# schematics.net
KiCad netlist of a schematic drawn in EasyEDA
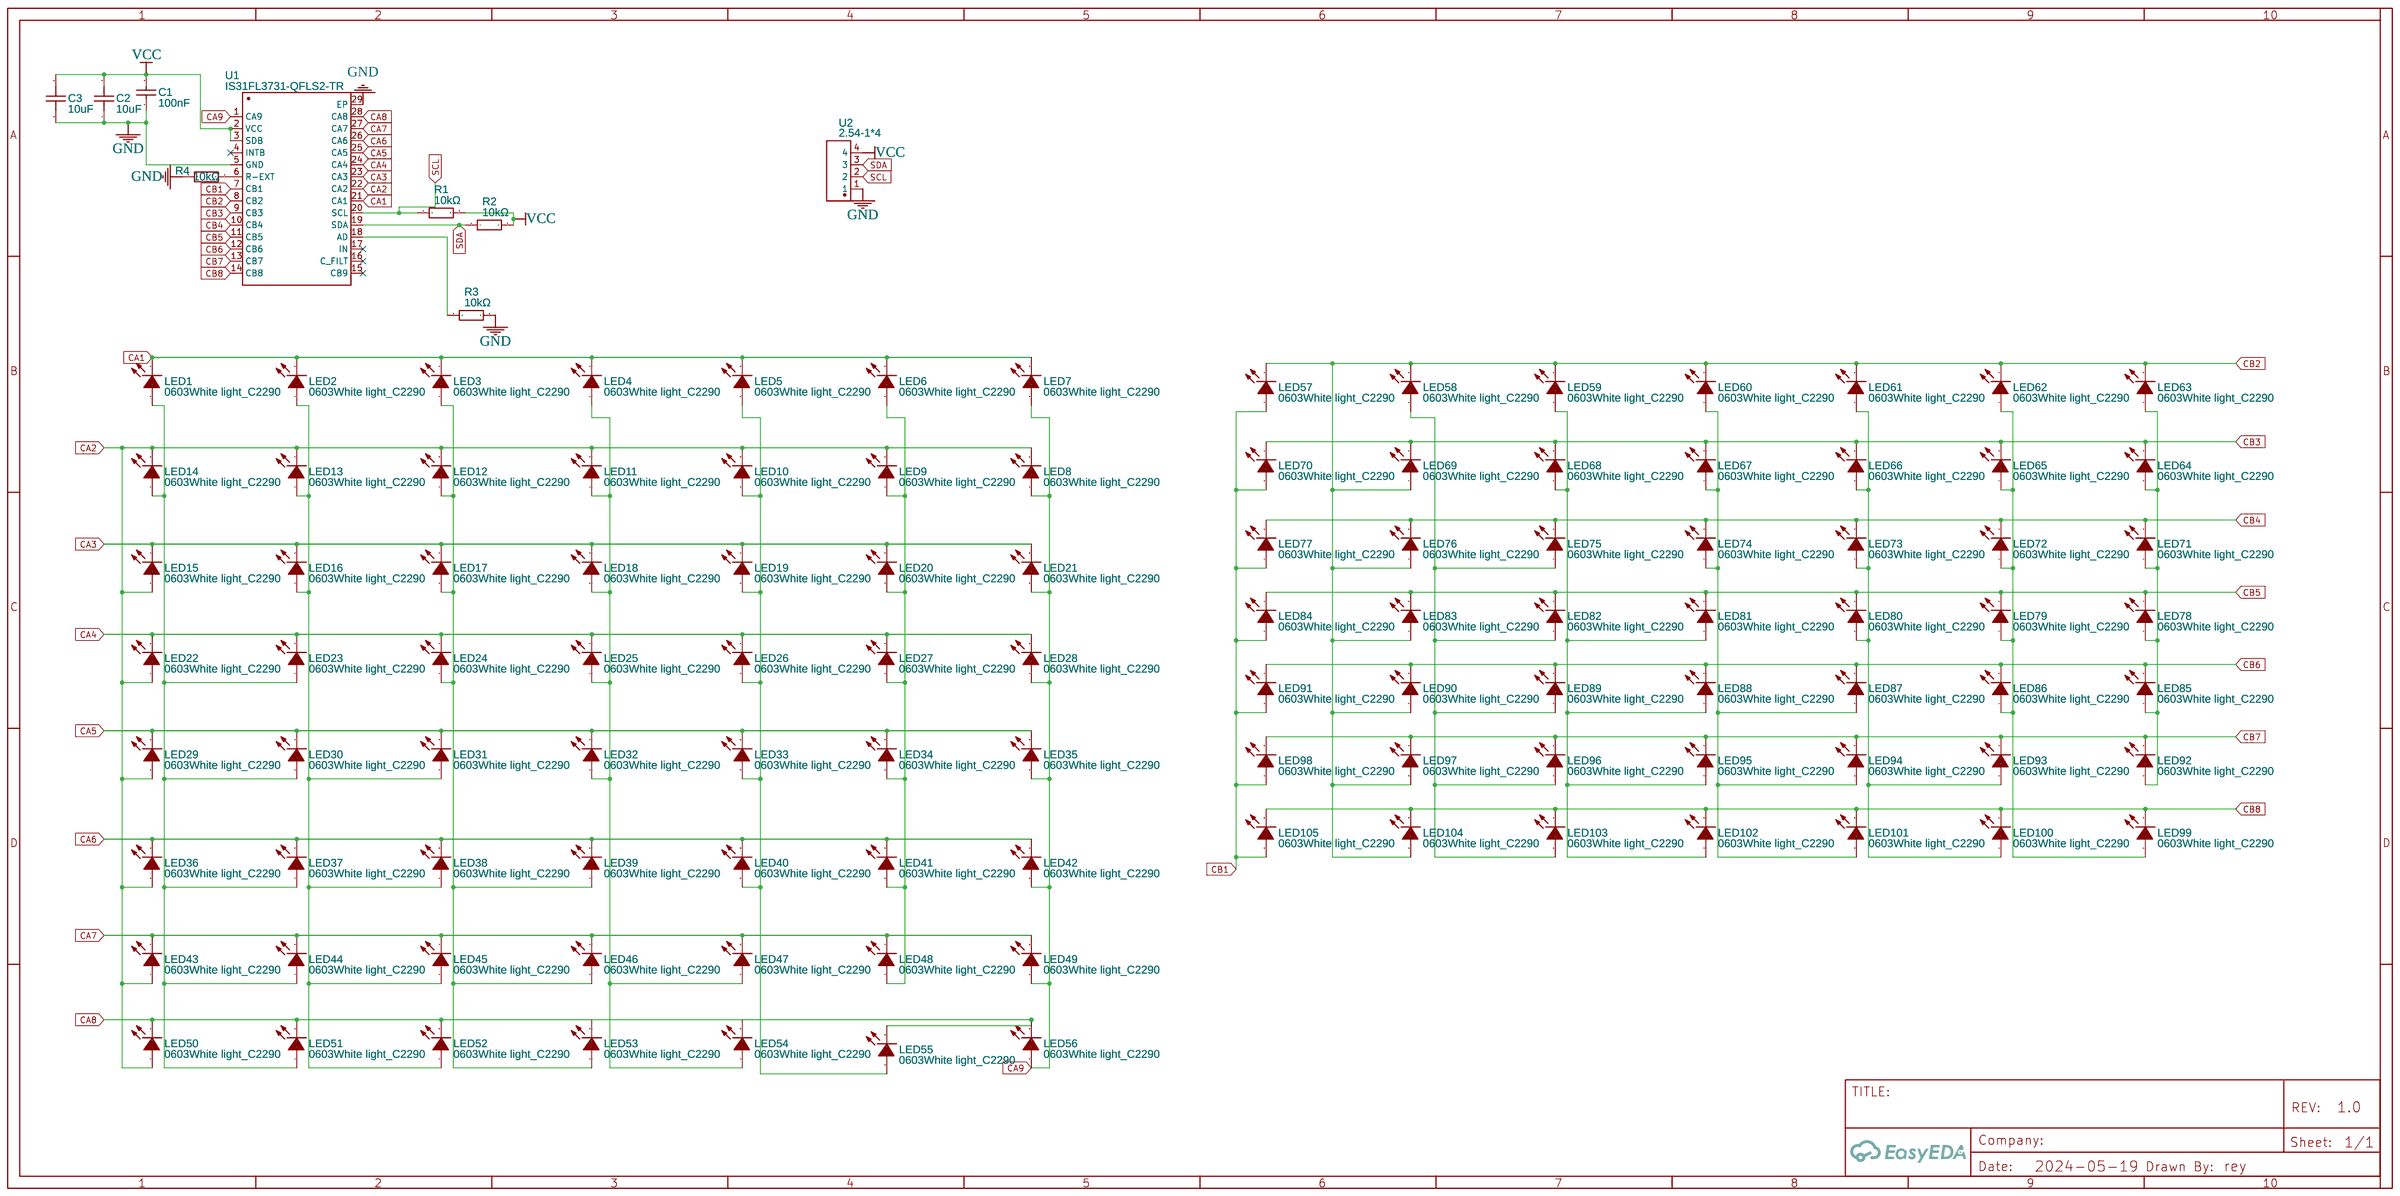
[diagram p0: schematic sheet]

(export (version "E")
  (design (tool "Eeschema 10.0.6"))
  (components
    (comp (ref "C1")
      (value "100nF")
      (fields
        (field (name "Manufacturer Part") "CL05B104KO5NNNC")
        (field (name "Manufacturer") "SAMSUNG(三星)")
      )
      (libsource (lib "") (part "CL05B104KO5NNNC"))
    )
    (comp (ref "C2")
      (value "10uF")
      (fields
        (field (name "Manufacturer Part") "CL10A106KP8NNNC")
        (field (name "Manufacturer") "SAMSUNG(三星)")
      )
      (libsource (lib "") (part "CL10A106KP8NNNC"))
    )
    (comp (ref "C3")
      (value "10uF")
      (fields
        (field (name "Manufacturer Part") "CL10A106KP8NNNC")
        (field (name "Manufacturer") "SAMSUNG(三星)")
      )
      (libsource (lib "") (part "CL10A106KP8NNNC"))
    )
    (comp (ref "LED1")
      (value "0603White light_C2290")
      (fields (field (name "Manufacturer Part") "KT-0603白灯") (field (name "Manufacturer") "KENTO"))
      (libsource (lib "") (part "0603White light_C2290"))
    )
    (comp (ref "LED2")
      (value "0603White light_C2290")
      (fields (field (name "Manufacturer Part") "KT-0603白灯") (field (name "Manufacturer") "KENTO"))
      (libsource (lib "") (part "0603White light_C2290"))
    )
    (comp (ref "LED3")
      (value "0603White light_C2290")
      (fields (field (name "Manufacturer Part") "KT-0603白灯") (field (name "Manufacturer") "KENTO"))
      (libsource (lib "") (part "0603White light_C2290"))
    )
    (comp (ref "LED4")
      (value "0603White light_C2290")
      (fields (field (name "Manufacturer Part") "KT-0603白灯") (field (name "Manufacturer") "KENTO"))
      (libsource (lib "") (part "0603White light_C2290"))
    )
    (comp (ref "LED5")
      (value "0603White light_C2290")
      (fields (field (name "Manufacturer Part") "KT-0603白灯") (field (name "Manufacturer") "KENTO"))
      (libsource (lib "") (part "0603White light_C2290"))
    )
    (comp (ref "LED6")
      (value "0603White light_C2290")
      (fields (field (name "Manufacturer Part") "KT-0603白灯") (field (name "Manufacturer") "KENTO"))
      (libsource (lib "") (part "0603White light_C2290"))
    )
    (comp (ref "LED7")
      (value "0603White light_C2290")
      (fields (field (name "Manufacturer Part") "KT-0603白灯") (field (name "Manufacturer") "KENTO"))
      (libsource (lib "") (part "0603White light_C2290"))
    )
    (comp (ref "LED8")
      (value "0603White light_C2290")
      (fields (field (name "Manufacturer Part") "KT-0603白灯") (field (name "Manufacturer") "KENTO"))
      (libsource (lib "") (part "0603White light_C2290"))
    )
    (comp (ref "LED9")
      (value "0603White light_C2290")
      (fields (field (name "Manufacturer Part") "KT-0603白灯") (field (name "Manufacturer") "KENTO"))
      (libsource (lib "") (part "0603White light_C2290"))
    )
    (comp (ref "LED10")
      (value "0603White light_C2290")
      (fields (field (name "Manufacturer Part") "KT-0603白灯") (field (name "Manufacturer") "KENTO"))
      (libsource (lib "") (part "0603White light_C2290"))
    )
    (comp (ref "LED11")
      (value "0603White light_C2290")
      (fields (field (name "Manufacturer Part") "KT-0603白灯") (field (name "Manufacturer") "KENTO"))
      (libsource (lib "") (part "0603White light_C2290"))
    )
    (comp (ref "LED12")
      (value "0603White light_C2290")
      (fields (field (name "Manufacturer Part") "KT-0603白灯") (field (name "Manufacturer") "KENTO"))
      (libsource (lib "") (part "0603White light_C2290"))
    )
    (comp (ref "LED13")
      (value "0603White light_C2290")
      (fields (field (name "Manufacturer Part") "KT-0603白灯") (field (name "Manufacturer") "KENTO"))
      (libsource (lib "") (part "0603White light_C2290"))
    )
    (comp (ref "LED14")
      (value "0603White light_C2290")
      (fields (field (name "Manufacturer Part") "KT-0603白灯") (field (name "Manufacturer") "KENTO"))
      (libsource (lib "") (part "0603White light_C2290"))
    )
    (comp (ref "LED15")
      (value "0603White light_C2290")
      (fields (field (name "Manufacturer Part") "KT-0603白灯") (field (name "Manufacturer") "KENTO"))
      (libsource (lib "") (part "0603White light_C2290"))
    )
    (comp (ref "LED16")
      (value "0603White light_C2290")
      (fields (field (name "Manufacturer Part") "KT-0603白灯") (field (name "Manufacturer") "KENTO"))
      (libsource (lib "") (part "0603White light_C2290"))
    )
    (comp (ref "LED17")
      (value "0603White light_C2290")
      (fields (field (name "Manufacturer Part") "KT-0603白灯") (field (name "Manufacturer") "KENTO"))
      (libsource (lib "") (part "0603White light_C2290"))
    )
    (comp (ref "LED18")
      (value "0603White light_C2290")
      (fields (field (name "Manufacturer Part") "KT-0603白灯") (field (name "Manufacturer") "KENTO"))
      (libsource (lib "") (part "0603White light_C2290"))
    )
    (comp (ref "LED19")
      (value "0603White light_C2290")
      (fields (field (name "Manufacturer Part") "KT-0603白灯") (field (name "Manufacturer") "KENTO"))
      (libsource (lib "") (part "0603White light_C2290"))
    )
    (comp (ref "LED20")
      (value "0603White light_C2290")
      (fields (field (name "Manufacturer Part") "KT-0603白灯") (field (name "Manufacturer") "KENTO"))
      (libsource (lib "") (part "0603White light_C2290"))
    )
    (comp (ref "LED21")
      (value "0603White light_C2290")
      (fields (field (name "Manufacturer Part") "KT-0603白灯") (field (name "Manufacturer") "KENTO"))
      (libsource (lib "") (part "0603White light_C2290"))
    )
    (comp (ref "LED22")
      (value "0603White light_C2290")
      (fields (field (name "Manufacturer Part") "KT-0603白灯") (field (name "Manufacturer") "KENTO"))
      (libsource (lib "") (part "0603White light_C2290"))
    )
    (comp (ref "LED23")
      (value "0603White light_C2290")
      (fields (field (name "Manufacturer Part") "KT-0603白灯") (field (name "Manufacturer") "KENTO"))
      (libsource (lib "") (part "0603White light_C2290"))
    )
    (comp (ref "LED24")
      (value "0603White light_C2290")
      (fields (field (name "Manufacturer Part") "KT-0603白灯") (field (name "Manufacturer") "KENTO"))
      (libsource (lib "") (part "0603White light_C2290"))
    )
    (comp (ref "LED25")
      (value "0603White light_C2290")
      (fields (field (name "Manufacturer Part") "KT-0603白灯") (field (name "Manufacturer") "KENTO"))
      (libsource (lib "") (part "0603White light_C2290"))
    )
    (comp (ref "LED26")
      (value "0603White light_C2290")
      (fields (field (name "Manufacturer Part") "KT-0603白灯") (field (name "Manufacturer") "KENTO"))
      (libsource (lib "") (part "0603White light_C2290"))
    )
    (comp (ref "LED27")
      (value "0603White light_C2290")
      (fields (field (name "Manufacturer Part") "KT-0603白灯") (field (name "Manufacturer") "KENTO"))
      (libsource (lib "") (part "0603White light_C2290"))
    )
    (comp (ref "LED28")
      (value "0603White light_C2290")
      (fields (field (name "Manufacturer Part") "KT-0603白灯") (field (name "Manufacturer") "KENTO"))
      (libsource (lib "") (part "0603White light_C2290"))
    )
    (comp (ref "LED29")
      (value "0603White light_C2290")
      (fields (field (name "Manufacturer Part") "KT-0603白灯") (field (name "Manufacturer") "KENTO"))
      (libsource (lib "") (part "0603White light_C2290"))
    )
    (comp (ref "LED30")
      (value "0603White light_C2290")
      (fields (field (name "Manufacturer Part") "KT-0603白灯") (field (name "Manufacturer") "KENTO"))
      (libsource (lib "") (part "0603White light_C2290"))
    )
    (comp (ref "LED31")
      (value "0603White light_C2290")
      (fields (field (name "Manufacturer Part") "KT-0603白灯") (field (name "Manufacturer") "KENTO"))
      (libsource (lib "") (part "0603White light_C2290"))
    )
    (comp (ref "LED32")
      (value "0603White light_C2290")
      (fields (field (name "Manufacturer Part") "KT-0603白灯") (field (name "Manufacturer") "KENTO"))
      (libsource (lib "") (part "0603White light_C2290"))
    )
    (comp (ref "LED33")
      (value "0603White light_C2290")
      (fields (field (name "Manufacturer Part") "KT-0603白灯") (field (name "Manufacturer") "KENTO"))
      (libsource (lib "") (part "0603White light_C2290"))
    )
    (comp (ref "LED34")
      (value "0603White light_C2290")
      (fields (field (name "Manufacturer Part") "KT-0603白灯") (field (name "Manufacturer") "KENTO"))
      (libsource (lib "") (part "0603White light_C2290"))
    )
    (comp (ref "LED35")
      (value "0603White light_C2290")
      (fields (field (name "Manufacturer Part") "KT-0603白灯") (field (name "Manufacturer") "KENTO"))
      (libsource (lib "") (part "0603White light_C2290"))
    )
    (comp (ref "LED36")
      (value "0603White light_C2290")
      (fields (field (name "Manufacturer Part") "KT-0603白灯") (field (name "Manufacturer") "KENTO"))
      (libsource (lib "") (part "0603White light_C2290"))
    )
    (comp (ref "LED37")
      (value "0603White light_C2290")
      (fields (field (name "Manufacturer Part") "KT-0603白灯") (field (name "Manufacturer") "KENTO"))
      (libsource (lib "") (part "0603White light_C2290"))
    )
    (comp (ref "LED38")
      (value "0603White light_C2290")
      (fields (field (name "Manufacturer Part") "KT-0603白灯") (field (name "Manufacturer") "KENTO"))
      (libsource (lib "") (part "0603White light_C2290"))
    )
    (comp (ref "LED39")
      (value "0603White light_C2290")
      (fields (field (name "Manufacturer Part") "KT-0603白灯") (field (name "Manufacturer") "KENTO"))
      (libsource (lib "") (part "0603White light_C2290"))
    )
    (comp (ref "LED40")
      (value "0603White light_C2290")
      (fields (field (name "Manufacturer Part") "KT-0603白灯") (field (name "Manufacturer") "KENTO"))
      (libsource (lib "") (part "0603White light_C2290"))
    )
    (comp (ref "LED41")
      (value "0603White light_C2290")
      (fields (field (name "Manufacturer Part") "KT-0603白灯") (field (name "Manufacturer") "KENTO"))
      (libsource (lib "") (part "0603White light_C2290"))
    )
    (comp (ref "LED42")
      (value "0603White light_C2290")
      (fields (field (name "Manufacturer Part") "KT-0603白灯") (field (name "Manufacturer") "KENTO"))
      (libsource (lib "") (part "0603White light_C2290"))
    )
    (comp (ref "LED43")
      (value "0603White light_C2290")
      (fields (field (name "Manufacturer Part") "KT-0603白灯") (field (name "Manufacturer") "KENTO"))
      (libsource (lib "") (part "0603White light_C2290"))
    )
    (comp (ref "LED44")
      (value "0603White light_C2290")
      (fields (field (name "Manufacturer Part") "KT-0603白灯") (field (name "Manufacturer") "KENTO"))
      (libsource (lib "") (part "0603White light_C2290"))
    )
    (comp (ref "LED45")
      (value "0603White light_C2290")
      (fields (field (name "Manufacturer Part") "KT-0603白灯") (field (name "Manufacturer") "KENTO"))
      (libsource (lib "") (part "0603White light_C2290"))
    )
    (comp (ref "LED46")
      (value "0603White light_C2290")
      (fields (field (name "Manufacturer Part") "KT-0603白灯") (field (name "Manufacturer") "KENTO"))
      (libsource (lib "") (part "0603White light_C2290"))
    )
    (comp (ref "LED47")
      (value "0603White light_C2290")
      (fields (field (name "Manufacturer Part") "KT-0603白灯") (field (name "Manufacturer") "KENTO"))
      (libsource (lib "") (part "0603White light_C2290"))
    )
    (comp (ref "LED48")
      (value "0603White light_C2290")
      (fields (field (name "Manufacturer Part") "KT-0603白灯") (field (name "Manufacturer") "KENTO"))
      (libsource (lib "") (part "0603White light_C2290"))
    )
    (comp (ref "LED49")
      (value "0603White light_C2290")
      (fields (field (name "Manufacturer Part") "KT-0603白灯") (field (name "Manufacturer") "KENTO"))
      (libsource (lib "") (part "0603White light_C2290"))
    )
    (comp (ref "LED50")
      (value "0603White light_C2290")
      (fields (field (name "Manufacturer Part") "KT-0603白灯") (field (name "Manufacturer") "KENTO"))
      (libsource (lib "") (part "0603White light_C2290"))
    )
    (comp (ref "LED51")
      (value "0603White light_C2290")
      (fields (field (name "Manufacturer Part") "KT-0603白灯") (field (name "Manufacturer") "KENTO"))
      (libsource (lib "") (part "0603White light_C2290"))
    )
    (comp (ref "LED52")
      (value "0603White light_C2290")
      (fields (field (name "Manufacturer Part") "KT-0603白灯") (field (name "Manufacturer") "KENTO"))
      (libsource (lib "") (part "0603White light_C2290"))
    )
    (comp (ref "LED53")
      (value "0603White light_C2290")
      (fields (field (name "Manufacturer Part") "KT-0603白灯") (field (name "Manufacturer") "KENTO"))
      (libsource (lib "") (part "0603White light_C2290"))
    )
    (comp (ref "LED54")
      (value "0603White light_C2290")
      (fields (field (name "Manufacturer Part") "KT-0603白灯") (field (name "Manufacturer") "KENTO"))
      (libsource (lib "") (part "0603White light_C2290"))
    )
    (comp (ref "LED55")
      (value "0603White light_C2290")
      (fields (field (name "Manufacturer Part") "KT-0603白灯") (field (name "Manufacturer") "KENTO"))
      (libsource (lib "") (part "0603White light_C2290"))
    )
    (comp (ref "LED56")
      (value "0603White light_C2290")
      (fields (field (name "Manufacturer Part") "KT-0603白灯") (field (name "Manufacturer") "KENTO"))
      (libsource (lib "") (part "0603White light_C2290"))
    )
    (comp (ref "LED57")
      (value "0603White light_C2290")
      (fields (field (name "Manufacturer Part") "KT-0603白灯") (field (name "Manufacturer") "KENTO"))
      (libsource (lib "") (part "0603White light_C2290_1"))
    )
    (comp (ref "LED58")
      (value "0603White light_C2290")
      (fields (field (name "Manufacturer Part") "KT-0603白灯") (field (name "Manufacturer") "KENTO"))
      (libsource (lib "") (part "0603White light_C2290_1"))
    )
    (comp (ref "LED59")
      (value "0603White light_C2290")
      (fields (field (name "Manufacturer Part") "KT-0603白灯") (field (name "Manufacturer") "KENTO"))
      (libsource (lib "") (part "0603White light_C2290_1"))
    )
    (comp (ref "LED60")
      (value "0603White light_C2290")
      (fields (field (name "Manufacturer Part") "KT-0603白灯") (field (name "Manufacturer") "KENTO"))
      (libsource (lib "") (part "0603White light_C2290_1"))
    )
    (comp (ref "LED61")
      (value "0603White light_C2290")
      (fields (field (name "Manufacturer Part") "KT-0603白灯") (field (name "Manufacturer") "KENTO"))
      (libsource (lib "") (part "0603White light_C2290_1"))
    )
    (comp (ref "LED62")
      (value "0603White light_C2290")
      (fields (field (name "Manufacturer Part") "KT-0603白灯") (field (name "Manufacturer") "KENTO"))
      (libsource (lib "") (part "0603White light_C2290_1"))
    )
    (comp (ref "LED63")
      (value "0603White light_C2290")
      (fields (field (name "Manufacturer Part") "KT-0603白灯") (field (name "Manufacturer") "KENTO"))
      (libsource (lib "") (part "0603White light_C2290_1"))
    )
    (comp (ref "LED64")
      (value "0603White light_C2290")
      (fields (field (name "Manufacturer Part") "KT-0603白灯") (field (name "Manufacturer") "KENTO"))
      (libsource (lib "") (part "0603White light_C2290_1"))
    )
    (comp (ref "LED65")
      (value "0603White light_C2290")
      (fields (field (name "Manufacturer Part") "KT-0603白灯") (field (name "Manufacturer") "KENTO"))
      (libsource (lib "") (part "0603White light_C2290_1"))
    )
    (comp (ref "LED66")
      (value "0603White light_C2290")
      (fields (field (name "Manufacturer Part") "KT-0603白灯") (field (name "Manufacturer") "KENTO"))
      (libsource (lib "") (part "0603White light_C2290_1"))
    )
    (comp (ref "LED67")
      (value "0603White light_C2290")
      (fields (field (name "Manufacturer Part") "KT-0603白灯") (field (name "Manufacturer") "KENTO"))
      (libsource (lib "") (part "0603White light_C2290_1"))
    )
    (comp (ref "LED68")
      (value "0603White light_C2290")
      (fields (field (name "Manufacturer Part") "KT-0603白灯") (field (name "Manufacturer") "KENTO"))
      (libsource (lib "") (part "0603White light_C2290_1"))
    )
    (comp (ref "LED69")
      (value "0603White light_C2290")
      (fields (field (name "Manufacturer Part") "KT-0603白灯") (field (name "Manufacturer") "KENTO"))
      (libsource (lib "") (part "0603White light_C2290_1"))
    )
    (comp (ref "LED70")
      (value "0603White light_C2290")
      (fields (field (name "Manufacturer Part") "KT-0603白灯") (field (name "Manufacturer") "KENTO"))
      (libsource (lib "") (part "0603White light_C2290_1"))
    )
    (comp (ref "LED71")
      (value "0603White light_C2290")
      (fields (field (name "Manufacturer Part") "KT-0603白灯") (field (name "Manufacturer") "KENTO"))
      (libsource (lib "") (part "0603White light_C2290_1"))
    )
    (comp (ref "LED72")
      (value "0603White light_C2290")
      (fields (field (name "Manufacturer Part") "KT-0603白灯") (field (name "Manufacturer") "KENTO"))
      (libsource (lib "") (part "0603White light_C2290_1"))
    )
    (comp (ref "LED73")
      (value "0603White light_C2290")
      (fields (field (name "Manufacturer Part") "KT-0603白灯") (field (name "Manufacturer") "KENTO"))
      (libsource (lib "") (part "0603White light_C2290_1"))
    )
    (comp (ref "LED74")
      (value "0603White light_C2290")
      (fields (field (name "Manufacturer Part") "KT-0603白灯") (field (name "Manufacturer") "KENTO"))
      (libsource (lib "") (part "0603White light_C2290_1"))
    )
    (comp (ref "LED75")
      (value "0603White light_C2290")
      (fields (field (name "Manufacturer Part") "KT-0603白灯") (field (name "Manufacturer") "KENTO"))
      (libsource (lib "") (part "0603White light_C2290_1"))
    )
    (comp (ref "LED76")
      (value "0603White light_C2290")
      (fields (field (name "Manufacturer Part") "KT-0603白灯") (field (name "Manufacturer") "KENTO"))
      (libsource (lib "") (part "0603White light_C2290_1"))
    )
    (comp (ref "LED77")
      (value "0603White light_C2290")
      (fields (field (name "Manufacturer Part") "KT-0603白灯") (field (name "Manufacturer") "KENTO"))
      (libsource (lib "") (part "0603White light_C2290_1"))
    )
    (comp (ref "LED78")
      (value "0603White light_C2290")
      (fields (field (name "Manufacturer Part") "KT-0603白灯") (field (name "Manufacturer") "KENTO"))
      (libsource (lib "") (part "0603White light_C2290_1"))
    )
    (comp (ref "LED79")
      (value "0603White light_C2290")
      (fields (field (name "Manufacturer Part") "KT-0603白灯") (field (name "Manufacturer") "KENTO"))
      (libsource (lib "") (part "0603White light_C2290_1"))
    )
    (comp (ref "LED80")
      (value "0603White light_C2290")
      (fields (field (name "Manufacturer Part") "KT-0603白灯") (field (name "Manufacturer") "KENTO"))
      (libsource (lib "") (part "0603White light_C2290_1"))
    )
    (comp (ref "LED81")
      (value "0603White light_C2290")
      (fields (field (name "Manufacturer Part") "KT-0603白灯") (field (name "Manufacturer") "KENTO"))
      (libsource (lib "") (part "0603White light_C2290_1"))
    )
    (comp (ref "LED82")
      (value "0603White light_C2290")
      (fields (field (name "Manufacturer Part") "KT-0603白灯") (field (name "Manufacturer") "KENTO"))
      (libsource (lib "") (part "0603White light_C2290_1"))
    )
    (comp (ref "LED83")
      (value "0603White light_C2290")
      (fields (field (name "Manufacturer Part") "KT-0603白灯") (field (name "Manufacturer") "KENTO"))
      (libsource (lib "") (part "0603White light_C2290_1"))
    )
    (comp (ref "LED84")
      (value "0603White light_C2290")
      (fields (field (name "Manufacturer Part") "KT-0603白灯") (field (name "Manufacturer") "KENTO"))
      (libsource (lib "") (part "0603White light_C2290_1"))
    )
    (comp (ref "LED85")
      (value "0603White light_C2290")
      (fields (field (name "Manufacturer Part") "KT-0603白灯") (field (name "Manufacturer") "KENTO"))
      (libsource (lib "") (part "0603White light_C2290_1"))
    )
    (comp (ref "LED86")
      (value "0603White light_C2290")
      (fields (field (name "Manufacturer Part") "KT-0603白灯") (field (name "Manufacturer") "KENTO"))
      (libsource (lib "") (part "0603White light_C2290_1"))
    )
    (comp (ref "LED87")
      (value "0603White light_C2290")
      (fields (field (name "Manufacturer Part") "KT-0603白灯") (field (name "Manufacturer") "KENTO"))
      (libsource (lib "") (part "0603White light_C2290_1"))
    )
    (comp (ref "LED88")
      (value "0603White light_C2290")
      (fields (field (name "Manufacturer Part") "KT-0603白灯") (field (name "Manufacturer") "KENTO"))
      (libsource (lib "") (part "0603White light_C2290_1"))
    )
    (comp (ref "LED89")
      (value "0603White light_C2290")
      (fields (field (name "Manufacturer Part") "KT-0603白灯") (field (name "Manufacturer") "KENTO"))
      (libsource (lib "") (part "0603White light_C2290_1"))
    )
    (comp (ref "LED90")
      (value "0603White light_C2290")
      (fields (field (name "Manufacturer Part") "KT-0603白灯") (field (name "Manufacturer") "KENTO"))
      (libsource (lib "") (part "0603White light_C2290_1"))
    )
    (comp (ref "LED91")
      (value "0603White light_C2290")
      (fields (field (name "Manufacturer Part") "KT-0603白灯") (field (name "Manufacturer") "KENTO"))
      (libsource (lib "") (part "0603White light_C2290_1"))
    )
    (comp (ref "LED92")
      (value "0603White light_C2290")
      (fields (field (name "Manufacturer Part") "KT-0603白灯") (field (name "Manufacturer") "KENTO"))
      (libsource (lib "") (part "0603White light_C2290_1"))
    )
    (comp (ref "LED93")
      (value "0603White light_C2290")
      (fields (field (name "Manufacturer Part") "KT-0603白灯") (field (name "Manufacturer") "KENTO"))
      (libsource (lib "") (part "0603White light_C2290_1"))
    )
    (comp (ref "LED94")
      (value "0603White light_C2290")
      (fields (field (name "Manufacturer Part") "KT-0603白灯") (field (name "Manufacturer") "KENTO"))
      (libsource (lib "") (part "0603White light_C2290_1"))
    )
    (comp (ref "LED95")
      (value "0603White light_C2290")
      (fields (field (name "Manufacturer Part") "KT-0603白灯") (field (name "Manufacturer") "KENTO"))
      (libsource (lib "") (part "0603White light_C2290_1"))
    )
    (comp (ref "LED96")
      (value "0603White light_C2290")
      (fields (field (name "Manufacturer Part") "KT-0603白灯") (field (name "Manufacturer") "KENTO"))
      (libsource (lib "") (part "0603White light_C2290_1"))
    )
    (comp (ref "LED97")
      (value "0603White light_C2290")
      (fields (field (name "Manufacturer Part") "KT-0603白灯") (field (name "Manufacturer") "KENTO"))
      (libsource (lib "") (part "0603White light_C2290_1"))
    )
    (comp (ref "LED98")
      (value "0603White light_C2290")
      (fields (field (name "Manufacturer Part") "KT-0603白灯") (field (name "Manufacturer") "KENTO"))
      (libsource (lib "") (part "0603White light_C2290_1"))
    )
    (comp (ref "LED99")
      (value "0603White light_C2290")
      (fields (field (name "Manufacturer Part") "KT-0603白灯") (field (name "Manufacturer") "KENTO"))
      (libsource (lib "") (part "0603White light_C2290_1"))
    )
    (comp (ref "LED100")
      (value "0603White light_C2290")
      (fields (field (name "Manufacturer Part") "KT-0603白灯") (field (name "Manufacturer") "KENTO"))
      (libsource (lib "") (part "0603White light_C2290_1"))
    )
    (comp (ref "LED101")
      (value "0603White light_C2290")
      (fields (field (name "Manufacturer Part") "KT-0603白灯") (field (name "Manufacturer") "KENTO"))
      (libsource (lib "") (part "0603White light_C2290_1"))
    )
    (comp (ref "LED102")
      (value "0603White light_C2290")
      (fields (field (name "Manufacturer Part") "KT-0603白灯") (field (name "Manufacturer") "KENTO"))
      (libsource (lib "") (part "0603White light_C2290_1"))
    )
    (comp (ref "LED103")
      (value "0603White light_C2290")
      (fields (field (name "Manufacturer Part") "KT-0603白灯") (field (name "Manufacturer") "KENTO"))
      (libsource (lib "") (part "0603White light_C2290_1"))
    )
    (comp (ref "LED104")
      (value "0603White light_C2290")
      (fields (field (name "Manufacturer Part") "KT-0603白灯") (field (name "Manufacturer") "KENTO"))
      (libsource (lib "") (part "0603White light_C2290_1"))
    )
    (comp (ref "LED105")
      (value "0603White light_C2290")
      (fields (field (name "Manufacturer Part") "KT-0603白灯") (field (name "Manufacturer") "KENTO"))
      (libsource (lib "") (part "0603White light_C2290_1"))
    )
    (comp (ref "R1")
      (value "10kΩ")
      (fields
        (field (name "Manufacturer Part") "0402WGF1002TCE")
        (field (name "Manufacturer") "UNI-ROYAL(厚声)")
      )
      (libsource (lib "") (part "0402WGF1002TCE"))
    )
    (comp (ref "R2")
      (value "10kΩ")
      (fields
        (field (name "Manufacturer Part") "0402WGF1002TCE")
        (field (name "Manufacturer") "UNI-ROYAL(厚声)")
      )
      (libsource (lib "") (part "0402WGF1002TCE"))
    )
    (comp (ref "R3")
      (value "10kΩ")
      (fields
        (field (name "Manufacturer Part") "0402WGF1002TCE")
        (field (name "Manufacturer") "UNI-ROYAL(厚声)")
      )
      (libsource (lib "") (part "0402WGF1002TCE"))
    )
    (comp (ref "R4")
      (value "10kΩ")
      (fields
        (field (name "Manufacturer Part") "0402WGF1002TCE")
        (field (name "Manufacturer") "UNI-ROYAL(厚声)")
      )
      (libsource (lib "") (part "0402WGF1002TCE"))
    )
    (comp (ref "U1")
      (value "IS31FL3731-QFLS2-TR")
      (fields (field (name "Manufacturer") "ISSI(美国芯成)"))
      (libsource (lib "") (part "IS31FL3731-QFLS2-TR"))
    )
    (comp (ref "U2")
      (value "2.54-1*4")
      (fields (field (name "Manufacturer") "ZHOURI(洲日)"))
      (libsource (lib "") (part "2.54-1*4"))
    )
  )
  (nets
    (net (code "1") (name "CA1") (class "Default")
      (node (ref "LED1") (pin "2") (pinfunction "K_2") (pintype "unspecified"))
      (node (ref "LED2") (pin "2") (pinfunction "K_2") (pintype "unspecified"))
      (node (ref "LED3") (pin "2") (pinfunction "K_2") (pintype "unspecified"))
      (node (ref "LED4") (pin "2") (pinfunction "K_2") (pintype "unspecified"))
      (node (ref "LED5") (pin "2") (pinfunction "K_2") (pintype "unspecified"))
      (node (ref "LED6") (pin "2") (pinfunction "K_2") (pintype "unspecified"))
      (node (ref "LED7") (pin "2") (pinfunction "K_2") (pintype "unspecified"))
      (node (ref "U1") (pin "21") (pinfunction "CA1_21") (pintype "unspecified"))
    )
    (net (code "2") (name "CA2") (class "Default")
      (node (ref "LED10") (pin "2") (pinfunction "K_2") (pintype "unspecified"))
      (node (ref "LED11") (pin "2") (pinfunction "K_2") (pintype "unspecified"))
      (node (ref "LED12") (pin "2") (pinfunction "K_2") (pintype "unspecified"))
      (node (ref "LED13") (pin "2") (pinfunction "K_2") (pintype "unspecified"))
      (node (ref "LED14") (pin "2") (pinfunction "K_2") (pintype "unspecified"))
      (node (ref "LED15") (pin "1") (pinfunction "A_1") (pintype "unspecified"))
      (node (ref "LED22") (pin "1") (pinfunction "A_1") (pintype "unspecified"))
      (node (ref "LED29") (pin "1") (pinfunction "A_1") (pintype "unspecified"))
      (node (ref "LED36") (pin "1") (pinfunction "A_1") (pintype "unspecified"))
      (node (ref "LED43") (pin "1") (pinfunction "A_1") (pintype "unspecified"))
      (node (ref "LED50") (pin "1") (pinfunction "A_1") (pintype "unspecified"))
      (node (ref "LED8") (pin "2") (pinfunction "K_2") (pintype "unspecified"))
      (node (ref "LED9") (pin "2") (pinfunction "K_2") (pintype "unspecified"))
      (node (ref "U1") (pin "22") (pinfunction "CA2_22") (pintype "unspecified"))
    )
    (net (code "3") (name "CA3") (class "Default")
      (node (ref "LED15") (pin "2") (pinfunction "K_2") (pintype "unspecified"))
      (node (ref "LED16") (pin "2") (pinfunction "K_2") (pintype "unspecified"))
      (node (ref "LED17") (pin "2") (pinfunction "K_2") (pintype "unspecified"))
      (node (ref "LED18") (pin "2") (pinfunction "K_2") (pintype "unspecified"))
      (node (ref "LED19") (pin "2") (pinfunction "K_2") (pintype "unspecified"))
      (node (ref "LED20") (pin "2") (pinfunction "K_2") (pintype "unspecified"))
      (node (ref "LED21") (pin "2") (pinfunction "K_2") (pintype "unspecified"))
      (node (ref "U1") (pin "23") (pinfunction "CA3_23") (pintype "unspecified"))
    )
    (net (code "4") (name "CA4") (class "Default")
      (node (ref "LED22") (pin "2") (pinfunction "K_2") (pintype "unspecified"))
      (node (ref "LED23") (pin "2") (pinfunction "K_2") (pintype "unspecified"))
      (node (ref "LED24") (pin "2") (pinfunction "K_2") (pintype "unspecified"))
      (node (ref "LED25") (pin "2") (pinfunction "K_2") (pintype "unspecified"))
      (node (ref "LED26") (pin "2") (pinfunction "K_2") (pintype "unspecified"))
      (node (ref "LED27") (pin "2") (pinfunction "K_2") (pintype "unspecified"))
      (node (ref "LED28") (pin "2") (pinfunction "K_2") (pintype "unspecified"))
      (node (ref "U1") (pin "24") (pinfunction "CA4_24") (pintype "unspecified"))
    )
    (net (code "5") (name "CA5") (class "Default")
      (node (ref "LED29") (pin "2") (pinfunction "K_2") (pintype "unspecified"))
      (node (ref "LED30") (pin "2") (pinfunction "K_2") (pintype "unspecified"))
      (node (ref "LED31") (pin "2") (pinfunction "K_2") (pintype "unspecified"))
      (node (ref "LED32") (pin "2") (pinfunction "K_2") (pintype "unspecified"))
      (node (ref "LED33") (pin "2") (pinfunction "K_2") (pintype "unspecified"))
      (node (ref "LED34") (pin "2") (pinfunction "K_2") (pintype "unspecified"))
      (node (ref "LED35") (pin "2") (pinfunction "K_2") (pintype "unspecified"))
      (node (ref "U1") (pin "25") (pinfunction "CA5_25") (pintype "unspecified"))
    )
    (net (code "6") (name "CA6") (class "Default")
      (node (ref "LED36") (pin "2") (pinfunction "K_2") (pintype "unspecified"))
      (node (ref "LED37") (pin "2") (pinfunction "K_2") (pintype "unspecified"))
      (node (ref "LED38") (pin "2") (pinfunction "K_2") (pintype "unspecified"))
      (node (ref "LED39") (pin "2") (pinfunction "K_2") (pintype "unspecified"))
      (node (ref "LED40") (pin "2") (pinfunction "K_2") (pintype "unspecified"))
      (node (ref "LED41") (pin "2") (pinfunction "K_2") (pintype "unspecified"))
      (node (ref "LED42") (pin "2") (pinfunction "K_2") (pintype "unspecified"))
      (node (ref "U1") (pin "26") (pinfunction "CA6_26") (pintype "unspecified"))
    )
    (net (code "7") (name "CA7") (class "Default")
      (node (ref "LED43") (pin "2") (pinfunction "K_2") (pintype "unspecified"))
      (node (ref "LED44") (pin "2") (pinfunction "K_2") (pintype "unspecified"))
      (node (ref "LED45") (pin "2") (pinfunction "K_2") (pintype "unspecified"))
      (node (ref "LED46") (pin "2") (pinfunction "K_2") (pintype "unspecified"))
      (node (ref "LED47") (pin "2") (pinfunction "K_2") (pintype "unspecified"))
      (node (ref "LED48") (pin "2") (pinfunction "K_2") (pintype "unspecified"))
      (node (ref "LED49") (pin "2") (pinfunction "K_2") (pintype "unspecified"))
      (node (ref "U1") (pin "27") (pinfunction "CA7_27") (pintype "unspecified"))
    )
    (net (code "8") (name "CA8") (class "Default")
      (node (ref "LED50") (pin "2") (pinfunction "K_2") (pintype "unspecified"))
      (node (ref "LED51") (pin "2") (pinfunction "K_2") (pintype "unspecified"))
      (node (ref "LED52") (pin "2") (pinfunction "K_2") (pintype "unspecified"))
      (node (ref "LED53") (pin "2") (pinfunction "K_2") (pintype "unspecified"))
      (node (ref "LED54") (pin "2") (pinfunction "K_2") (pintype "unspecified"))
      (node (ref "LED55") (pin "2") (pinfunction "K_2") (pintype "unspecified"))
      (node (ref "LED56") (pin "2") (pinfunction "K_2") (pintype "unspecified"))
      (node (ref "U1") (pin "28") (pinfunction "CA8_28") (pintype "unspecified"))
    )
    (net (code "9") (name "CA9") (class "Default")
      (node (ref "LED21") (pin "1") (pinfunction "A_1") (pintype "unspecified"))
      (node (ref "LED28") (pin "1") (pinfunction "A_1") (pintype "unspecified"))
      (node (ref "LED35") (pin "1") (pinfunction "A_1") (pintype "unspecified"))
      (node (ref "LED42") (pin "1") (pinfunction "A_1") (pintype "unspecified"))
      (node (ref "LED49") (pin "1") (pinfunction "A_1") (pintype "unspecified"))
      (node (ref "LED56") (pin "1") (pinfunction "A_1") (pintype "unspecified"))
      (node (ref "LED7") (pin "1") (pinfunction "A_1") (pintype "unspecified"))
      (node (ref "LED8") (pin "1") (pinfunction "A_1") (pintype "unspecified"))
      (node (ref "U1") (pin "1") (pinfunction "CA9_1") (pintype "unspecified"))
    )
    (net (code "10") (name "CB1") (class "Default")
      (node (ref "LED105") (pin "1") (pinfunction "A_1") (pintype "unspecified"))
      (node (ref "LED57") (pin "1") (pinfunction "A_1") (pintype "unspecified"))
      (node (ref "LED70") (pin "1") (pinfunction "A_1") (pintype "unspecified"))
      (node (ref "LED77") (pin "1") (pinfunction "A_1") (pintype "unspecified"))
      (node (ref "LED84") (pin "1") (pinfunction "A_1") (pintype "unspecified"))
      (node (ref "LED91") (pin "1") (pinfunction "A_1") (pintype "unspecified"))
      (node (ref "LED98") (pin "1") (pinfunction "A_1") (pintype "unspecified"))
      (node (ref "U1") (pin "7") (pinfunction "CB1_7") (pintype "unspecified"))
    )
    (net (code "11") (name "CB2") (class "Default")
      (node (ref "LED104") (pin "1") (pinfunction "A_1") (pintype "unspecified"))
      (node (ref "LED57") (pin "2") (pinfunction "K_2") (pintype "unspecified"))
      (node (ref "LED58") (pin "2") (pinfunction "K_2") (pintype "unspecified"))
      (node (ref "LED59") (pin "2") (pinfunction "K_2") (pintype "unspecified"))
      (node (ref "LED60") (pin "2") (pinfunction "K_2") (pintype "unspecified"))
      (node (ref "LED61") (pin "2") (pinfunction "K_2") (pintype "unspecified"))
      (node (ref "LED62") (pin "2") (pinfunction "K_2") (pintype "unspecified"))
      (node (ref "LED63") (pin "2") (pinfunction "K_2") (pintype "unspecified"))
      (node (ref "LED69") (pin "1") (pinfunction "A_1") (pintype "unspecified"))
      (node (ref "LED76") (pin "1") (pinfunction "A_1") (pintype "unspecified"))
      (node (ref "LED83") (pin "1") (pinfunction "A_1") (pintype "unspecified"))
      (node (ref "LED90") (pin "1") (pinfunction "A_1") (pintype "unspecified"))
      (node (ref "LED97") (pin "1") (pinfunction "A_1") (pintype "unspecified"))
      (node (ref "U1") (pin "8") (pinfunction "CB2_8") (pintype "unspecified"))
    )
    (net (code "12") (name "CB3") (class "Default")
      (node (ref "LED64") (pin "2") (pinfunction "K_2") (pintype "unspecified"))
      (node (ref "LED65") (pin "2") (pinfunction "K_2") (pintype "unspecified"))
      (node (ref "LED66") (pin "2") (pinfunction "K_2") (pintype "unspecified"))
      (node (ref "LED67") (pin "2") (pinfunction "K_2") (pintype "unspecified"))
      (node (ref "LED68") (pin "2") (pinfunction "K_2") (pintype "unspecified"))
      (node (ref "LED69") (pin "2") (pinfunction "K_2") (pintype "unspecified"))
      (node (ref "LED70") (pin "2") (pinfunction "K_2") (pintype "unspecified"))
      (node (ref "U1") (pin "9") (pinfunction "CB3_9") (pintype "unspecified"))
    )
    (net (code "13") (name "CB4") (class "Default")
      (node (ref "LED71") (pin "2") (pinfunction "K_2") (pintype "unspecified"))
      (node (ref "LED72") (pin "2") (pinfunction "K_2") (pintype "unspecified"))
      (node (ref "LED73") (pin "2") (pinfunction "K_2") (pintype "unspecified"))
      (node (ref "LED74") (pin "2") (pinfunction "K_2") (pintype "unspecified"))
      (node (ref "LED75") (pin "2") (pinfunction "K_2") (pintype "unspecified"))
      (node (ref "LED76") (pin "2") (pinfunction "K_2") (pintype "unspecified"))
      (node (ref "LED77") (pin "2") (pinfunction "K_2") (pintype "unspecified"))
      (node (ref "U1") (pin "10") (pinfunction "CB4_10") (pintype "unspecified"))
    )
    (net (code "14") (name "CB5") (class "Default")
      (node (ref "LED78") (pin "2") (pinfunction "K_2") (pintype "unspecified"))
      (node (ref "LED79") (pin "2") (pinfunction "K_2") (pintype "unspecified"))
      (node (ref "LED80") (pin "2") (pinfunction "K_2") (pintype "unspecified"))
      (node (ref "LED81") (pin "2") (pinfunction "K_2") (pintype "unspecified"))
      (node (ref "LED82") (pin "2") (pinfunction "K_2") (pintype "unspecified"))
      (node (ref "LED83") (pin "2") (pinfunction "K_2") (pintype "unspecified"))
      (node (ref "LED84") (pin "2") (pinfunction "K_2") (pintype "unspecified"))
      (node (ref "U1") (pin "11") (pinfunction "CB5_11") (pintype "unspecified"))
    )
    (net (code "15") (name "CB6") (class "Default")
      (node (ref "LED85") (pin "2") (pinfunction "K_2") (pintype "unspecified"))
      (node (ref "LED86") (pin "2") (pinfunction "K_2") (pintype "unspecified"))
      (node (ref "LED87") (pin "2") (pinfunction "K_2") (pintype "unspecified"))
      (node (ref "LED88") (pin "2") (pinfunction "K_2") (pintype "unspecified"))
      (node (ref "LED89") (pin "2") (pinfunction "K_2") (pintype "unspecified"))
      (node (ref "LED90") (pin "2") (pinfunction "K_2") (pintype "unspecified"))
      (node (ref "LED91") (pin "2") (pinfunction "K_2") (pintype "unspecified"))
      (node (ref "U1") (pin "12") (pinfunction "CB6_12") (pintype "unspecified"))
    )
    (net (code "16") (name "CB7") (class "Default")
      (node (ref "LED92") (pin "2") (pinfunction "K_2") (pintype "unspecified"))
      (node (ref "LED93") (pin "2") (pinfunction "K_2") (pintype "unspecified"))
      (node (ref "LED94") (pin "2") (pinfunction "K_2") (pintype "unspecified"))
      (node (ref "LED95") (pin "2") (pinfunction "K_2") (pintype "unspecified"))
      (node (ref "LED96") (pin "2") (pinfunction "K_2") (pintype "unspecified"))
      (node (ref "LED97") (pin "2") (pinfunction "K_2") (pintype "unspecified"))
      (node (ref "LED98") (pin "2") (pinfunction "K_2") (pintype "unspecified"))
      (node (ref "U1") (pin "13") (pinfunction "CB7_13") (pintype "unspecified"))
    )
    (net (code "17") (name "CB8") (class "Default")
      (node (ref "LED100") (pin "2") (pinfunction "K_2") (pintype "unspecified"))
      (node (ref "LED101") (pin "2") (pinfunction "K_2") (pintype "unspecified"))
      (node (ref "LED102") (pin "2") (pinfunction "K_2") (pintype "unspecified"))
      (node (ref "LED103") (pin "2") (pinfunction "K_2") (pintype "unspecified"))
      (node (ref "LED104") (pin "2") (pinfunction "K_2") (pintype "unspecified"))
      (node (ref "LED105") (pin "2") (pinfunction "K_2") (pintype "unspecified"))
      (node (ref "LED99") (pin "2") (pinfunction "K_2") (pintype "unspecified"))
      (node (ref "U1") (pin "14") (pinfunction "CB8_14") (pintype "unspecified"))
    )
    (net (code "18") (name "GND") (class "Default")
      (node (ref "C1") (pin "1") (pinfunction "1_1") (pintype "input"))
      (node (ref "C2") (pin "1") (pinfunction "1_1") (pintype "unspecified"))
      (node (ref "C3") (pin "1") (pinfunction "1_1") (pintype "unspecified"))
      (node (ref "R3") (pin "2") (pinfunction "2_2") (pintype "input"))
      (node (ref "R4") (pin "1") (pinfunction "1_1") (pintype "input"))
      (node (ref "U1") (pin "29") (pinfunction "EP_29") (pintype "unspecified"))
      (node (ref "U1") (pin "5") (pinfunction "GND_5") (pintype "unspecified"))
      (node (ref "U2") (pin "1") (pinfunction "1_1") (pintype "unspecified"))
    )
    (net (code "19") (name "Net-(LED1-A)") (class "Default")
      (node (ref "LED1") (pin "1") (pinfunction "A_1") (pintype "unspecified"))
      (node (ref "LED14") (pin "1") (pinfunction "A_1") (pintype "unspecified"))
      (node (ref "LED23") (pin "1") (pinfunction "A_1") (pintype "unspecified"))
      (node (ref "LED30") (pin "1") (pinfunction "A_1") (pintype "unspecified"))
      (node (ref "LED37") (pin "1") (pinfunction "A_1") (pintype "unspecified"))
      (node (ref "LED44") (pin "1") (pinfunction "A_1") (pintype "unspecified"))
      (node (ref "LED51") (pin "1") (pinfunction "A_1") (pintype "unspecified"))
    )
    (net (code "20") (name "Net-(LED10-A)") (class "Default")
      (node (ref "LED10") (pin "1") (pinfunction "A_1") (pintype "unspecified"))
      (node (ref "LED19") (pin "1") (pinfunction "A_1") (pintype "unspecified"))
      (node (ref "LED26") (pin "1") (pinfunction "A_1") (pintype "unspecified"))
      (node (ref "LED33") (pin "1") (pinfunction "A_1") (pintype "unspecified"))
      (node (ref "LED40") (pin "1") (pinfunction "A_1") (pintype "unspecified"))
      (node (ref "LED5") (pin "1") (pinfunction "A_1") (pintype "unspecified"))
      (node (ref "LED55") (pin "1") (pinfunction "A_1") (pintype "unspecified"))
    )
    (net (code "21") (name "Net-(LED11-A)") (class "Default")
      (node (ref "LED11") (pin "1") (pinfunction "A_1") (pintype "unspecified"))
      (node (ref "LED18") (pin "1") (pinfunction "A_1") (pintype "unspecified"))
      (node (ref "LED25") (pin "1") (pinfunction "A_1") (pintype "unspecified"))
      (node (ref "LED32") (pin "1") (pinfunction "A_1") (pintype "unspecified"))
      (node (ref "LED4") (pin "1") (pinfunction "A_1") (pintype "unspecified"))
      (node (ref "LED47") (pin "1") (pinfunction "A_1") (pintype "unspecified"))
      (node (ref "LED54") (pin "1") (pinfunction "A_1") (pintype "unspecified"))
    )
    (net (code "22") (name "Net-(LED12-A)") (class "Default")
      (node (ref "LED12") (pin "1") (pinfunction "A_1") (pintype "unspecified"))
      (node (ref "LED17") (pin "1") (pinfunction "A_1") (pintype "unspecified"))
      (node (ref "LED24") (pin "1") (pinfunction "A_1") (pintype "unspecified"))
      (node (ref "LED3") (pin "1") (pinfunction "A_1") (pintype "unspecified"))
      (node (ref "LED39") (pin "1") (pinfunction "A_1") (pintype "unspecified"))
      (node (ref "LED46") (pin "1") (pinfunction "A_1") (pintype "unspecified"))
      (node (ref "LED53") (pin "1") (pinfunction "A_1") (pintype "unspecified"))
    )
    (net (code "23") (name "Net-(LED13-A)") (class "Default")
      (node (ref "LED13") (pin "1") (pinfunction "A_1") (pintype "unspecified"))
      (node (ref "LED16") (pin "1") (pinfunction "A_1") (pintype "unspecified"))
      (node (ref "LED2") (pin "1") (pinfunction "A_1") (pintype "unspecified"))
      (node (ref "LED31") (pin "1") (pinfunction "A_1") (pintype "unspecified"))
      (node (ref "LED38") (pin "1") (pinfunction "A_1") (pintype "unspecified"))
      (node (ref "LED45") (pin "1") (pinfunction "A_1") (pintype "unspecified"))
      (node (ref "LED52") (pin "1") (pinfunction "A_1") (pintype "unspecified"))
    )
    (net (code "24") (name "Net-(LED20-A)") (class "Default")
      (node (ref "LED20") (pin "1") (pinfunction "A_1") (pintype "unspecified"))
      (node (ref "LED27") (pin "1") (pinfunction "A_1") (pintype "unspecified"))
      (node (ref "LED34") (pin "1") (pinfunction "A_1") (pintype "unspecified"))
      (node (ref "LED41") (pin "1") (pinfunction "A_1") (pintype "unspecified"))
      (node (ref "LED48") (pin "1") (pinfunction "A_1") (pintype "unspecified"))
      (node (ref "LED6") (pin "1") (pinfunction "A_1") (pintype "unspecified"))
      (node (ref "LED9") (pin "1") (pinfunction "A_1") (pintype "unspecified"))
    )
    (net (code "25") (name "Net-(LED62-A)") (class "Default")
      (node (ref "LED62") (pin "1") (pinfunction "A_1") (pintype "unspecified"))
      (node (ref "LED65") (pin "1") (pinfunction "A_1") (pintype "unspecified"))
      (node (ref "LED72") (pin "1") (pinfunction "A_1") (pintype "unspecified"))
      (node (ref "LED79") (pin "1") (pinfunction "A_1") (pintype "unspecified"))
      (node (ref "LED86") (pin "1") (pinfunction "A_1") (pintype "unspecified"))
      (node (ref "LED99") (pin "1") (pinfunction "A_1") (pintype "unspecified"))
    )
    (net (code "26") (name "Net-(LED63-A)") (class "Default")
      (node (ref "LED63") (pin "1") (pinfunction "A_1") (pintype "unspecified"))
      (node (ref "LED64") (pin "1") (pinfunction "A_1") (pintype "unspecified"))
      (node (ref "LED71") (pin "1") (pinfunction "A_1") (pintype "unspecified"))
      (node (ref "LED78") (pin "1") (pinfunction "A_1") (pintype "unspecified"))
      (node (ref "LED85") (pin "1") (pinfunction "A_1") (pintype "unspecified"))
      (node (ref "LED92") (pin "1") (pinfunction "A_1") (pintype "unspecified"))
    )
    (net (code "27") (name "Net-(LED100-A)") (class "Default")
      (node (ref "LED100") (pin "1") (pinfunction "A_1") (pintype "unspecified"))
      (node (ref "LED61") (pin "1") (pinfunction "A_1") (pintype "unspecified"))
      (node (ref "LED66") (pin "1") (pinfunction "A_1") (pintype "unspecified"))
      (node (ref "LED73") (pin "1") (pinfunction "A_1") (pintype "unspecified"))
      (node (ref "LED80") (pin "1") (pinfunction "A_1") (pintype "unspecified"))
      (node (ref "LED93") (pin "1") (pinfunction "A_1") (pintype "unspecified"))
    )
    (net (code "28") (name "Net-(LED101-A)") (class "Default")
      (node (ref "LED101") (pin "1") (pinfunction "A_1") (pintype "unspecified"))
      (node (ref "LED60") (pin "1") (pinfunction "A_1") (pintype "unspecified"))
      (node (ref "LED67") (pin "1") (pinfunction "A_1") (pintype "unspecified"))
      (node (ref "LED74") (pin "1") (pinfunction "A_1") (pintype "unspecified"))
      (node (ref "LED87") (pin "1") (pinfunction "A_1") (pintype "unspecified"))
      (node (ref "LED94") (pin "1") (pinfunction "A_1") (pintype "unspecified"))
    )
    (net (code "29") (name "Net-(LED102-A)") (class "Default")
      (node (ref "LED102") (pin "1") (pinfunction "A_1") (pintype "unspecified"))
      (node (ref "LED59") (pin "1") (pinfunction "A_1") (pintype "unspecified"))
      (node (ref "LED68") (pin "1") (pinfunction "A_1") (pintype "unspecified"))
      (node (ref "LED81") (pin "1") (pinfunction "A_1") (pintype "unspecified"))
      (node (ref "LED88") (pin "1") (pinfunction "A_1") (pintype "unspecified"))
      (node (ref "LED95") (pin "1") (pinfunction "A_1") (pintype "unspecified"))
    )
    (net (code "30") (name "Net-(LED103-A)") (class "Default")
      (node (ref "LED103") (pin "1") (pinfunction "A_1") (pintype "unspecified"))
      (node (ref "LED58") (pin "1") (pinfunction "A_1") (pintype "unspecified"))
      (node (ref "LED75") (pin "1") (pinfunction "A_1") (pintype "unspecified"))
      (node (ref "LED82") (pin "1") (pinfunction "A_1") (pintype "unspecified"))
      (node (ref "LED89") (pin "1") (pinfunction "A_1") (pintype "unspecified"))
      (node (ref "LED96") (pin "1") (pinfunction "A_1") (pintype "unspecified"))
    )
    (net (code "31") (name "Net-(U1-AD)") (class "Default")
      (node (ref "R3") (pin "1") (pinfunction "1_1") (pintype "input"))
      (node (ref "U1") (pin "18") (pinfunction "AD_18") (pintype "unspecified"))
    )
    (net (code "32") (name "Net-(U1-R-EXT)") (class "Default")
      (node (ref "R4") (pin "2") (pinfunction "2_2") (pintype "input"))
      (node (ref "U1") (pin "6") (pinfunction "R-EXT_6") (pintype "unspecified"))
    )
    (net (code "33") (name "SCL") (class "Default")
      (node (ref "R1") (pin "1") (pinfunction "1_1") (pintype "input"))
      (node (ref "U1") (pin "20") (pinfunction "SCL_20") (pintype "unspecified"))
      (node (ref "U2") (pin "2") (pinfunction "2_2") (pintype "unspecified"))
    )
    (net (code "34") (name "SDA") (class "Default")
      (node (ref "R2") (pin "1") (pinfunction "1_1") (pintype "input"))
      (node (ref "U1") (pin "19") (pinfunction "SDA_19") (pintype "unspecified"))
      (node (ref "U2") (pin "3") (pinfunction "3_3") (pintype "unspecified"))
    )
    (net (code "35") (name "VCC") (class "Default")
      (node (ref "C1") (pin "2") (pinfunction "2_2") (pintype "input"))
      (node (ref "C2") (pin "2") (pinfunction "2_2") (pintype "unspecified"))
      (node (ref "C3") (pin "2") (pinfunction "2_2") (pintype "unspecified"))
      (node (ref "R1") (pin "2") (pinfunction "2_2") (pintype "input"))
      (node (ref "R2") (pin "2") (pinfunction "2_2") (pintype "input"))
      (node (ref "U1") (pin "2") (pinfunction "VCC_2") (pintype "unspecified"))
      (node (ref "U1") (pin "3") (pinfunction "SDB_3") (pintype "unspecified"))
      (node (ref "U2") (pin "4") (pinfunction "4_4") (pintype "unspecified"))
    )
    (net (code "36") (name "unconnected-(U1-CB9-Pad15)") (class "Default")
      (node (ref "U1") (pin "15") (pinfunction "CB9_15") (pintype "unspecified+no_connect"))
    )
    (net (code "37") (name "unconnected-(U1-C_FILT-Pad16)") (class "Default")
      (node (ref "U1") (pin "16") (pinfunction "C_FILT_16") (pintype "unspecified+no_connect"))
    )
    (net (code "38") (name "unconnected-(U1-IN-Pad17)") (class "Default")
      (node (ref "U1") (pin "17") (pinfunction "IN_17") (pintype "unspecified+no_connect"))
    )
    (net (code "39") (name "unconnected-(U1-INTB-Pad4)") (class "Default")
      (node (ref "U1") (pin "4") (pinfunction "INTB_4") (pintype "unspecified+no_connect"))
    )
  )
)
